# Sheet1.net
KiCad netlist of a schematic drawn in Altium Designer
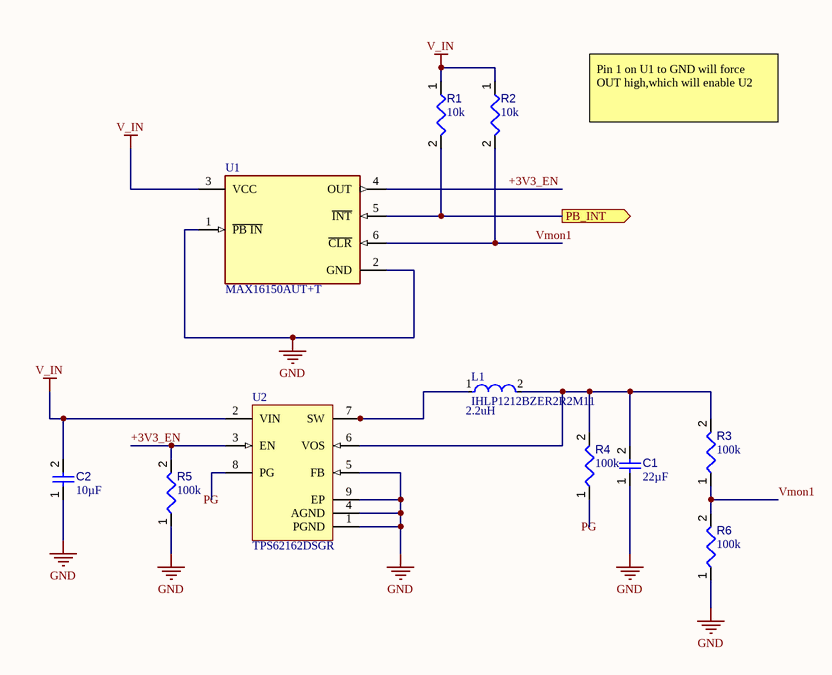
[diagram p0: Sheet1.SchDoc]

(export (version "E")
  (design (tool "Eeschema 10.0.6"))
  (components
    (comp (ref "C1")
      (value "22µF")
      (footprint "CAPC0805(2012)145_L")
      (description "Chip Capacitor, 22µF +/-40%, 16V, 0805, Thickness 1.45 mm")
      (fields (field (name "TOLERANCE") "5%") (field (name "Comment") "Capacitor 22µF +/-40% 16V 0805"))
      (libsource (lib "Pushpitha Kavinda") (part "CAP-NP-2"))
    )
    (comp (ref "C2")
      (value "10µF")
      (footprint "CAPC0603(1608)100_L")
      (description "Chip Capacitor, 10µF +/-20%, 10V, 0603, Thickness 1 mm")
      (fields (field (name "TOLERANCE") "10%") (field (name "Comment") "Capacitor 10µF +/-20% 10V 0603"))
      (libsource (lib "Pushpitha Kavinda") (part "CAP-NP-2"))
    )
    (comp (ref "L1")
      (value "IHLP1212BZER2R2M11")
      (footprint "FP-IHLP-1212BZ-11-MFG")
      (description "FIXED IND 2.2UH 3A 46 MOHM SMD")
      (fields (field (name "INDUCTANCE") "2.2uH") (field (name "TOLERANCE") "20%"))
      (libsource (lib "Altium Content Vault") (part "725321dda6339637d4d059423bc1c3c"))
    )
    (comp (ref "R1")
      (value "10k")
      (footprint "RESC0402(1005)_L")
      (description "Chip Resistor, 10 kOhms, +/-1 %, 63 mW, -55 to 125 degC, 0402")
      (fields (field (name "POWER") "63mW") (field (name "TOLERANCE") "1%"))
      (libsource (lib "Pushpitha Kavinda") (part "RES-2"))
    )
    (comp (ref "R2")
      (value "10k")
      (footprint "RESC0402(1005)_L")
      (description "Chip Resistor, 10 kOhms, +/-1 %, 63 mW, -55 to 125 degC, 0402")
      (fields (field (name "POWER") "63mW") (field (name "TOLERANCE") "1%"))
      (libsource (lib "Pushpitha Kavinda") (part "RES-2"))
    )
    (comp (ref "R3")
      (value "100k")
      (footprint "RESC0402(1005)_L")
      (description "Chip Resistor, 100 kOhms, +/-1 %, 63 mW, -55 to 155 degC, 0402")
      (fields (field (name "TOLERANCE") "1%") (field (name "POWER") "63mW"))
      (libsource (lib "Pushpitha Kavinda") (part "RES-2"))
    )
    (comp (ref "R4")
      (value "100k")
      (footprint "RESC0402(1005)_L")
      (description "Chip Resistor, 100 kOhms, +/-1 %, 63 mW, -55 to 155 degC, 0402")
      (fields (field (name "TOLERANCE") "1%") (field (name "POWER") "63mW"))
      (libsource (lib "Pushpitha Kavinda") (part "RES-2"))
    )
    (comp (ref "R5")
      (value "100k")
      (footprint "RESC0402(1005)_L")
      (description "Chip Resistor, 100 kOhms, +/-1 %, 63 mW, -55 to 155 degC, 0402")
      (fields (field (name "TOLERANCE") "1%") (field (name "POWER") "63mW"))
      (libsource (lib "Pushpitha Kavinda") (part "RES-2"))
    )
    (comp (ref "R6")
      (value "100k")
      (footprint "RESC0402(1005)_L")
      (description "Chip Resistor, 100 kOhms, +/-1 %, 63 mW, -55 to 155 degC, 0402")
      (fields (field (name "TOLERANCE") "1%") (field (name "POWER") "63mW"))
      (libsource (lib "Pushpitha Kavinda") (part "RES-2"))
    )
    (comp (ref "U1")
      (value "MAX16150AUT+T")
      (footprint "FP-U6-1-MFG")
      (description "IC SUPERVISOR 1 CHANNEL SOT23-6")
      (libsource (lib "Altium Content Vault") (part "36a392858d03d148bb8ce7f45f4b5f9"))
    )
    (comp (ref "U2")
      (value "TPS62162DSGR")
      (footprint "DSG0008A_V")
      (fields (field (name "MANUFACTURER") "Texas Instruments"))
      (libsource (lib "Altium Content Vault") (part "TI-TPS62162DSG8-1600X900TP"))
    )
  )
  (nets
    (net (code "1") (name "/+3V3_EN") (class "Default")
      (node (ref "R5") (pin "2") (pinfunction "2_2") (pintype "passive"))
      (node (ref "U1") (pin "4") (pinfunction "OUT_4") (pintype "output"))
      (node (ref "U2") (pin "3") (pinfunction "EN_3") (pintype "input"))
    )
    (net (code "2") (name "/PB_INT") (class "Default")
      (node (ref "R1") (pin "2") (pinfunction "2_2") (pintype "passive"))
      (node (ref "U1") (pin "5") (pinfunction "~{INT}_5") (pintype "input"))
    )
    (net (code "3") (name "/PG") (class "Default")
      (node (ref "R4") (pin "1") (pinfunction "1_1") (pintype "passive"))
      (node (ref "U2") (pin "8") (pinfunction "PG_8") (pintype "tri_state"))
    )
    (net (code "4") (name "/Vmon1") (class "Default")
      (node (ref "R2") (pin "2") (pinfunction "2_2") (pintype "passive"))
      (node (ref "R3") (pin "1") (pinfunction "1_1") (pintype "passive"))
      (node (ref "R6") (pin "2") (pinfunction "2_2") (pintype "passive"))
      (node (ref "U1") (pin "6") (pinfunction "~{CLR}_6") (pintype "input"))
    )
    (net (code "5") (name "GND") (class "Default")
      (node (ref "C1") (pin "1") (pinfunction "1_1") (pintype "passive"))
      (node (ref "C2") (pin "1") (pinfunction "1_1") (pintype "passive"))
      (node (ref "R5") (pin "1") (pinfunction "1_1") (pintype "passive"))
      (node (ref "R6") (pin "1") (pinfunction "1_1") (pintype "passive"))
      (node (ref "U1") (pin "1") (pinfunction "~{PB_IN}_1") (pintype "input"))
      (node (ref "U1") (pin "2") (pinfunction "GND_2") (pintype "power_in"))
      (node (ref "U2") (pin "1") (pinfunction "PGND_1") (pintype "power_in"))
      (node (ref "U2") (pin "4") (pinfunction "AGND_4") (pintype "power_in"))
      (node (ref "U2") (pin "5") (pinfunction "FB_5") (pintype "input"))
      (node (ref "U2") (pin "9") (pinfunction "EP_9") (pintype "power_in"))
    )
    (net (code "6") (name "Net-(U2-SW)") (class "Default")
      (node (ref "L1") (pin "1") (pinfunction "1_1") (pintype "passive"))
      (node (ref "U2") (pin "7") (pinfunction "SW_7") (pintype "power_in"))
    )
    (net (code "7") (name "Net-(U2-VOS)") (class "Default")
      (node (ref "C1") (pin "2") (pinfunction "2_2") (pintype "passive"))
      (node (ref "L1") (pin "2") (pinfunction "2_2") (pintype "passive"))
      (node (ref "R3") (pin "2") (pinfunction "2_2") (pintype "passive"))
      (node (ref "R4") (pin "2") (pinfunction "2_2") (pintype "passive"))
      (node (ref "U2") (pin "6") (pinfunction "VOS_6") (pintype "input"))
    )
    (net (code "8") (name "V_IN") (class "Default")
      (node (ref "C2") (pin "2") (pinfunction "2_2") (pintype "passive"))
      (node (ref "R1") (pin "1") (pinfunction "1_1") (pintype "passive"))
      (node (ref "R2") (pin "1") (pinfunction "1_1") (pintype "passive"))
      (node (ref "U1") (pin "3") (pinfunction "VCC_3") (pintype "power_in"))
      (node (ref "U2") (pin "2") (pinfunction "VIN_2") (pintype "power_in"))
    )
  )
)
